# GrblPiStepperDrivers.net
KiCad netlist of a schematic drawn in EAGLE
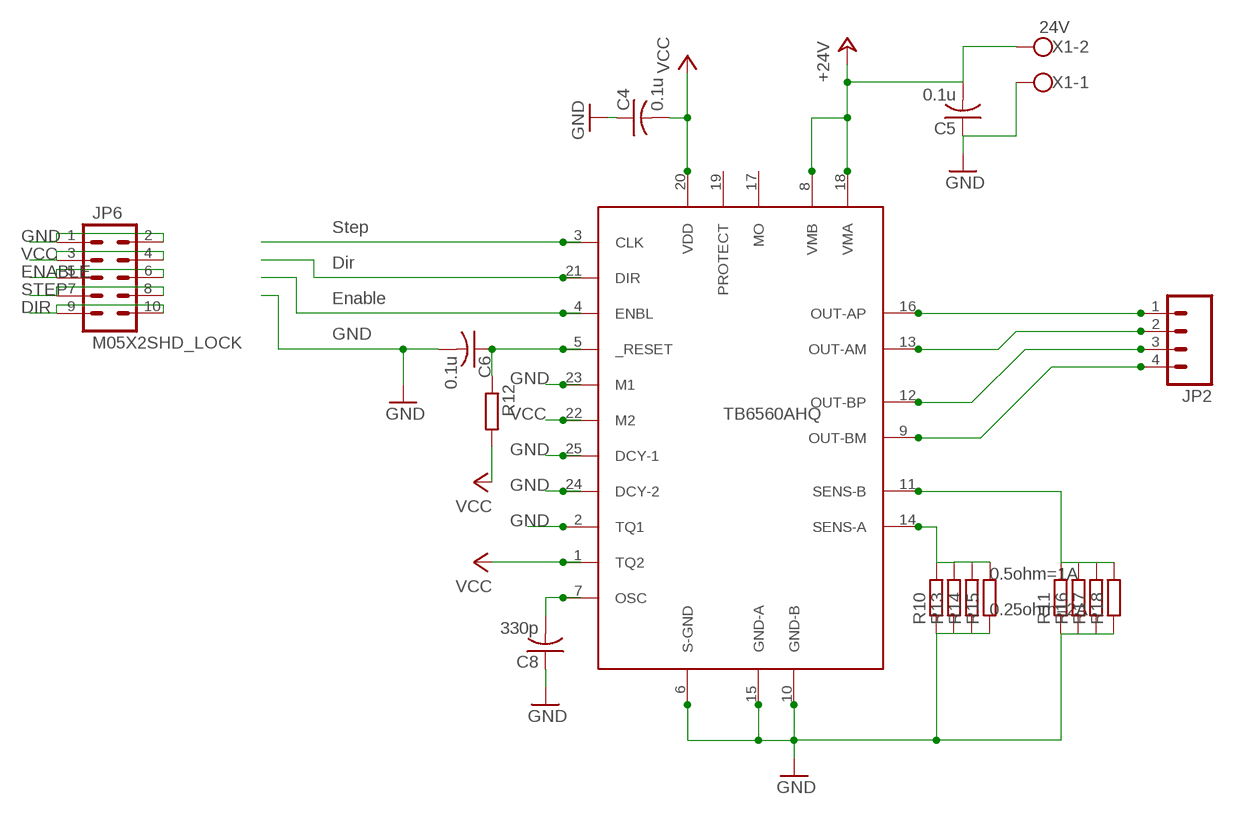
[diagram p0: schematic, sheet 1]

(export (version "E")
  (design (tool "Eeschema 10.0.6"))
  (components
    (comp (ref "C4")
      (value "0.1u")
      (footprint "eagle-import:C1206K")
      (libsource (lib "eagle-import") (part "C-USC1206K"))
    )
    (comp (ref "C5")
      (value "0.1u")
      (footprint "eagle-import:C1206K")
      (libsource (lib "eagle-import") (part "C-USC1206K"))
    )
    (comp (ref "C6")
      (value "0.1u")
      (footprint "eagle-import:C1206K")
      (libsource (lib "eagle-import") (part "C-USC1206K"))
    )
    (comp (ref "C8")
      (value "330p")
      (footprint "eagle-import:C1206K")
      (libsource (lib "eagle-import") (part "C-USC1206K"))
    )
    (comp (ref "JP2")
      (value "M04SCREW")
      (footprint "eagle-import:SCREWTERMINAL-3.5MM-4")
      (libsource (lib "eagle-import") (part "M04SCREW"))
    )
    (comp (ref "JP6")
      (value "M05X2SHD_LOCK")
      (footprint "eagle-import:2X5-SHROUDED_LOCK")
      (libsource (lib "eagle-import") (part "M05X2SHD_LOCK"))
    )
    (comp (ref "R10")
      (value "R-EU_0411/3V")
      (footprint "eagle-import:0411V")
      (libsource (lib "eagle-import") (part "R-EU_0411/3V"))
    )
    (comp (ref "R11")
      (value "R-EU_0411/3V")
      (footprint "eagle-import:0411V")
      (libsource (lib "eagle-import") (part "R-EU_0411/3V"))
    )
    (comp (ref "R12")
      (value "R-EU_M1206")
      (footprint "eagle-import:M1206")
      (libsource (lib "eagle-import") (part "rcl_R-EU_M1206"))
    )
    (comp (ref "R13")
      (value "R-EU_0411/3V")
      (footprint "eagle-import:0411V")
      (libsource (lib "eagle-import") (part "R-EU_0411/3V"))
    )
    (comp (ref "R14")
      (value "R-EU_0411/3V")
      (footprint "eagle-import:0411V")
      (libsource (lib "eagle-import") (part "R-EU_0411/3V"))
    )
    (comp (ref "R15")
      (value "R-EU_0411/3V")
      (footprint "eagle-import:0411V")
      (libsource (lib "eagle-import") (part "R-EU_0411/3V"))
    )
    (comp (ref "R16")
      (value "R-EU_0411/3V")
      (footprint "eagle-import:0411V")
      (libsource (lib "eagle-import") (part "R-EU_0411/3V"))
    )
    (comp (ref "R17")
      (value "R-EU_0411/3V")
      (footprint "eagle-import:0411V")
      (libsource (lib "eagle-import") (part "R-EU_0411/3V"))
    )
    (comp (ref "R18")
      (value "R-EU_0411/3V")
      (footprint "eagle-import:0411V")
      (libsource (lib "eagle-import") (part "R-EU_0411/3V"))
    )
    (comp (ref "U$2")
      (value "TB6560-H")
      (footprint "eagle-import:ZIP25-H")
      (libsource (lib "eagle-import") (part "TB6560-H"))
    )
    (comp (ref "X1")
      (value "24V")
      (footprint "eagle-import:W237-102")
      (fields (field (name "MPN") "237-102"))
      (libsource (lib "eagle-import") (part "W237-102"))
    )
  )
  (nets
    (net (code "1") (name "+24V") (class "Default")
      (node (ref "C5") (pin "2") (pinfunction "2_2") (pintype "passive"))
      (node (ref "U$2") (pin "18") (pinfunction "VMA_18") (pintype "bidirectional"))
      (node (ref "U$2") (pin "8") (pinfunction "VMB_8") (pintype "bidirectional"))
      (node (ref "X1") (pin "2") (pinfunction "KL_2") (pintype "passive"))
    )
    (net (code "2") (name "/DIR") (class "Default")
      (node (ref "JP6") (pin "10") (pinfunction "10_10") (pintype "passive"))
      (node (ref "JP6") (pin "9") (pinfunction "9_9") (pintype "passive"))
      (node (ref "U$2") (pin "21") (pinfunction "DIR_21") (pintype "bidirectional"))
    )
    (net (code "3") (name "/ENABLE") (class "Default")
      (node (ref "JP6") (pin "5") (pinfunction "5_5") (pintype "passive"))
      (node (ref "JP6") (pin "6") (pinfunction "6_6") (pintype "passive"))
      (node (ref "U$2") (pin "4") (pinfunction "ENBL_4") (pintype "bidirectional"))
    )
    (net (code "4") (name "/STEP") (class "Default")
      (node (ref "JP6") (pin "7") (pinfunction "7_7") (pintype "passive"))
      (node (ref "JP6") (pin "8") (pinfunction "8_8") (pintype "passive"))
      (node (ref "U$2") (pin "3") (pinfunction "CLK_3") (pintype "bidirectional"))
    )
    (net (code "5") (name "GND") (class "Default")
      (node (ref "C4") (pin "1") (pinfunction "1_1") (pintype "passive"))
      (node (ref "C5") (pin "1") (pinfunction "1_1") (pintype "passive"))
      (node (ref "C6") (pin "2") (pinfunction "2_2") (pintype "passive"))
      (node (ref "C8") (pin "1") (pinfunction "1_1") (pintype "passive"))
      (node (ref "JP6") (pin "1") (pinfunction "1_1") (pintype "passive"))
      (node (ref "JP6") (pin "2") (pinfunction "2_2") (pintype "passive"))
      (node (ref "R10") (pin "1") (pinfunction "1_1") (pintype "passive"))
      (node (ref "R11") (pin "1") (pinfunction "1_1") (pintype "passive"))
      (node (ref "R13") (pin "1") (pinfunction "1_1") (pintype "passive"))
      (node (ref "R14") (pin "1") (pinfunction "1_1") (pintype "passive"))
      (node (ref "R15") (pin "1") (pinfunction "1_1") (pintype "passive"))
      (node (ref "R16") (pin "1") (pinfunction "1_1") (pintype "passive"))
      (node (ref "R17") (pin "1") (pinfunction "1_1") (pintype "passive"))
      (node (ref "R18") (pin "1") (pinfunction "1_1") (pintype "passive"))
      (node (ref "U$2") (pin "10") (pinfunction "GND-B_10") (pintype "bidirectional"))
      (node (ref "U$2") (pin "15") (pinfunction "GND-A_15") (pintype "bidirectional"))
      (node (ref "U$2") (pin "2") (pinfunction "TQ1_2") (pintype "bidirectional"))
      (node (ref "U$2") (pin "23") (pinfunction "M1_23") (pintype "bidirectional"))
      (node (ref "U$2") (pin "24") (pinfunction "DCY-2_24") (pintype "bidirectional"))
      (node (ref "U$2") (pin "25") (pinfunction "DCY-1_25") (pintype "bidirectional"))
      (node (ref "U$2") (pin "6") (pinfunction "S-GND_6") (pintype "bidirectional"))
      (node (ref "X1") (pin "1") (pinfunction "KL_1") (pintype "passive"))
    )
    (net (code "6") (name "Net-(U$2-OSC)") (class "Default")
      (node (ref "C8") (pin "2") (pinfunction "2_2") (pintype "passive"))
      (node (ref "U$2") (pin "7") (pinfunction "OSC_7") (pintype "bidirectional"))
    )
    (net (code "7") (name "Net-(U$2-OUT-AM)") (class "Default")
      (node (ref "JP2") (pin "2") (pinfunction "2_2") (pintype "passive"))
      (node (ref "U$2") (pin "13") (pinfunction "OUT-AM_13") (pintype "output"))
    )
    (net (code "8") (name "Net-(U$2-OUT-AP)") (class "Default")
      (node (ref "JP2") (pin "1") (pinfunction "1_1") (pintype "passive"))
      (node (ref "U$2") (pin "16") (pinfunction "OUT-AP_16") (pintype "output"))
    )
    (net (code "9") (name "Net-(U$2-OUT-BM)") (class "Default")
      (node (ref "JP2") (pin "4") (pinfunction "4_4") (pintype "passive"))
      (node (ref "U$2") (pin "9") (pinfunction "OUT-BM_9") (pintype "output"))
    )
    (net (code "10") (name "Net-(U$2-OUT-BP)") (class "Default")
      (node (ref "JP2") (pin "3") (pinfunction "3_3") (pintype "passive"))
      (node (ref "U$2") (pin "12") (pinfunction "OUT-BP_12") (pintype "output"))
    )
    (net (code "11") (name "Net-(U$2-SENS-A)") (class "Default")
      (node (ref "R10") (pin "2") (pinfunction "2_2") (pintype "passive"))
      (node (ref "R13") (pin "2") (pinfunction "2_2") (pintype "passive"))
      (node (ref "R14") (pin "2") (pinfunction "2_2") (pintype "passive"))
      (node (ref "R15") (pin "2") (pinfunction "2_2") (pintype "passive"))
      (node (ref "U$2") (pin "14") (pinfunction "SENS-A_14") (pintype "bidirectional"))
    )
    (net (code "12") (name "Net-(U$2-SENS-B)") (class "Default")
      (node (ref "R11") (pin "2") (pinfunction "2_2") (pintype "passive"))
      (node (ref "R16") (pin "2") (pinfunction "2_2") (pintype "passive"))
      (node (ref "R17") (pin "2") (pinfunction "2_2") (pintype "passive"))
      (node (ref "R18") (pin "2") (pinfunction "2_2") (pintype "passive"))
      (node (ref "U$2") (pin "11") (pinfunction "SENS-B_11") (pintype "bidirectional"))
    )
    (net (code "13") (name "Net-(U$2-_RESET)") (class "Default")
      (node (ref "C6") (pin "1") (pinfunction "1_1") (pintype "passive"))
      (node (ref "R12") (pin "1") (pinfunction "1_1") (pintype "passive"))
      (node (ref "U$2") (pin "5") (pinfunction "_RESET_5") (pintype "bidirectional"))
    )
    (net (code "14") (name "VCC") (class "Default")
      (node (ref "C4") (pin "2") (pinfunction "2_2") (pintype "passive"))
      (node (ref "JP6") (pin "3") (pinfunction "3_3") (pintype "passive"))
      (node (ref "JP6") (pin "4") (pinfunction "4_4") (pintype "passive"))
      (node (ref "R12") (pin "2") (pinfunction "2_2") (pintype "passive"))
      (node (ref "U$2") (pin "1") (pinfunction "TQ2_1") (pintype "bidirectional"))
      (node (ref "U$2") (pin "20") (pinfunction "VDD_20") (pintype "bidirectional"))
      (node (ref "U$2") (pin "22") (pinfunction "M2_22") (pintype "bidirectional"))
    )
    (net (code "15") (name "unconnected-(U$2-MO-Pad17)") (class "Default")
      (node (ref "U$2") (pin "17") (pinfunction "MO_17") (pintype "bidirectional"))
    )
    (net (code "16") (name "unconnected-(U$2-PROTECT-Pad19)") (class "Default")
      (node (ref "U$2") (pin "19") (pinfunction "PROTECT_19") (pintype "bidirectional"))
    )
  )
)
